# theremin_PCB.net
KiCad netlist of a schematic drawn in EAGLE
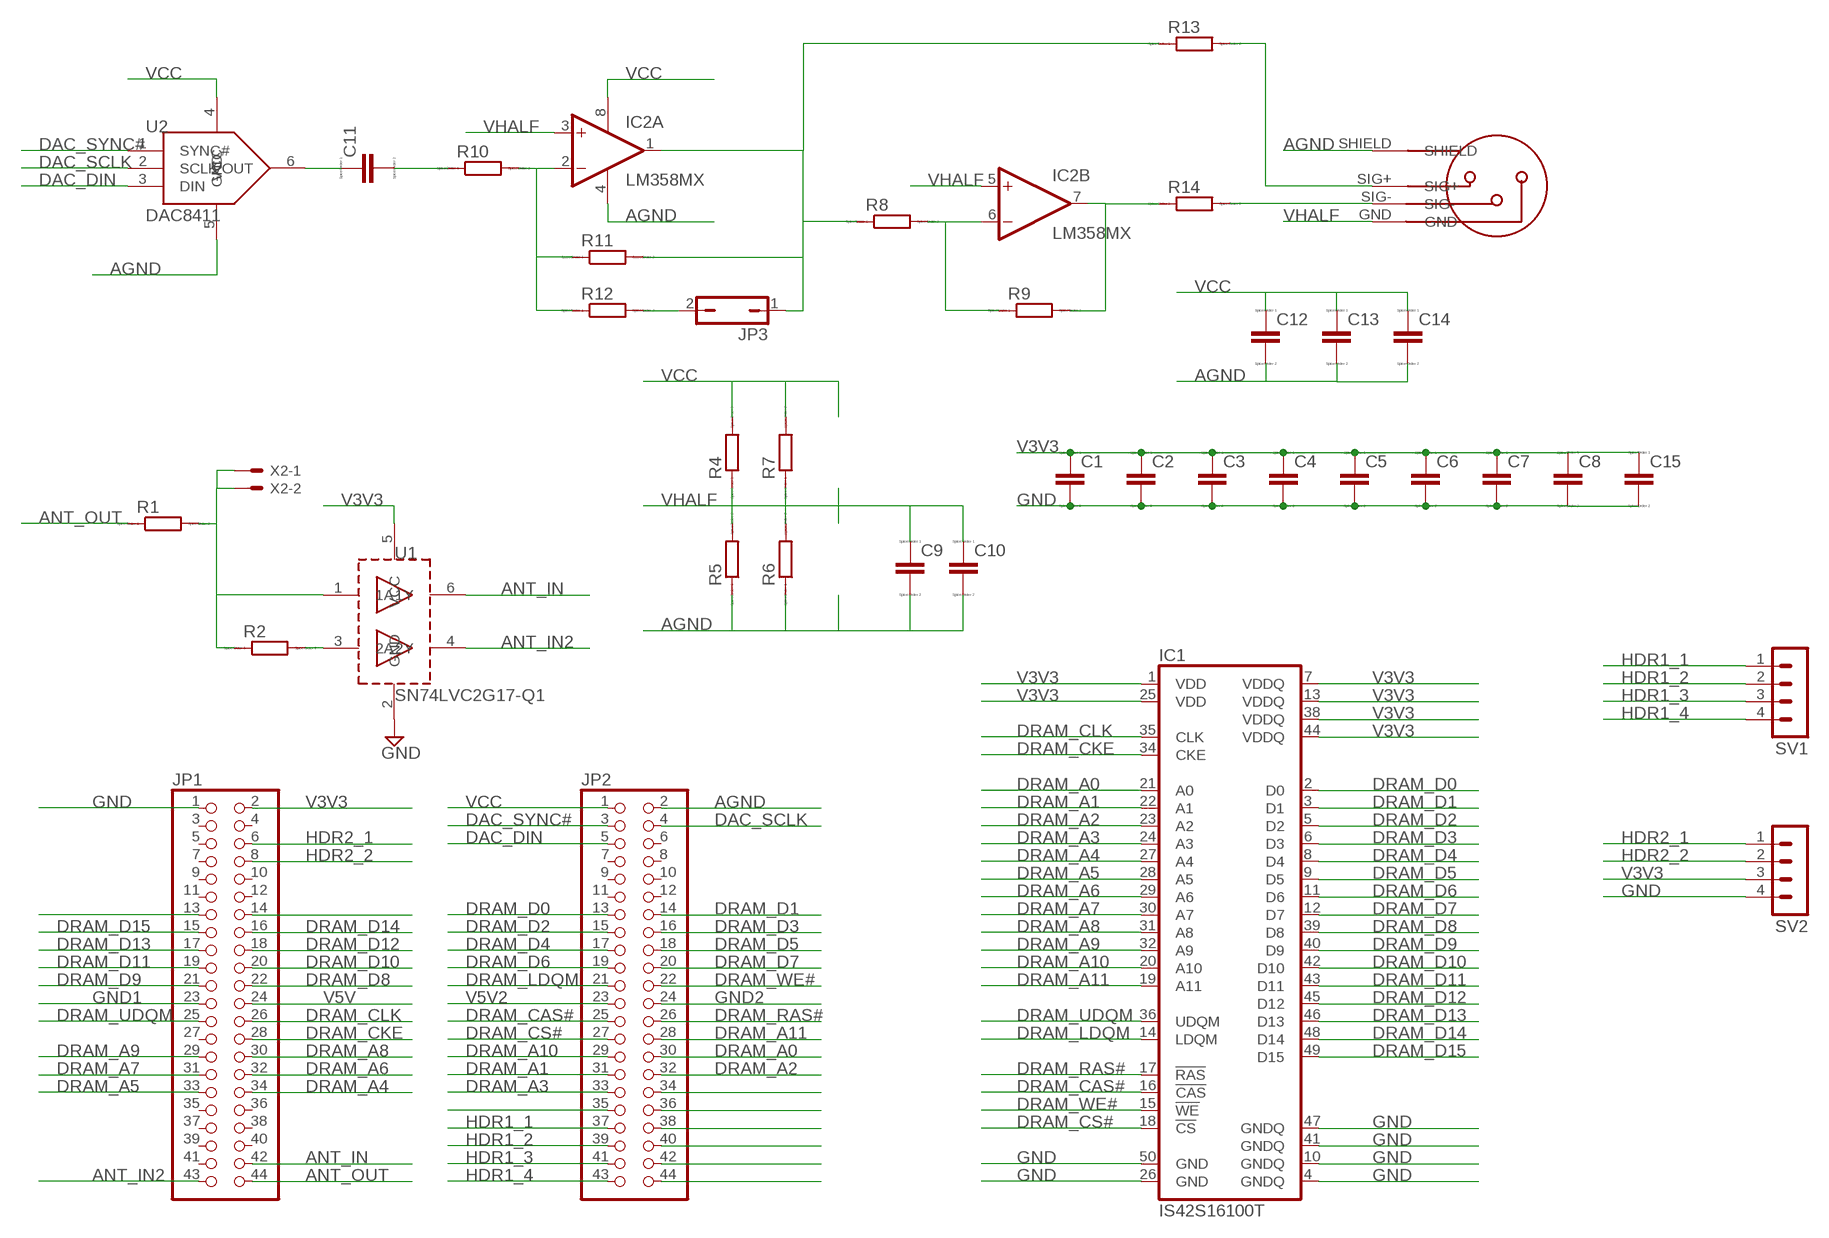
[diagram p0: schematic, sheet 1]

(export (version "E")
  (design (tool "Eeschema 10.0.6"))
  (components
    (comp (ref "C1")
      (value "C-EUC0805")
      (footprint "eagle-import:C0805")
      (libsource (lib "eagle-import") (part "C-EUC0805"))
    )
    (comp (ref "C2")
      (value "C-EUC0805")
      (footprint "eagle-import:C0805")
      (libsource (lib "eagle-import") (part "C-EUC0805"))
    )
    (comp (ref "C3")
      (value "C-EUC0805")
      (footprint "eagle-import:C0805")
      (libsource (lib "eagle-import") (part "C-EUC0805"))
    )
    (comp (ref "C4")
      (value "C-EUC0805")
      (footprint "eagle-import:C0805")
      (libsource (lib "eagle-import") (part "C-EUC0805"))
    )
    (comp (ref "C5")
      (value "C-EUC0805")
      (footprint "eagle-import:C0805")
      (libsource (lib "eagle-import") (part "C-EUC0805"))
    )
    (comp (ref "C6")
      (value "C-EUC0805")
      (footprint "eagle-import:C0805")
      (libsource (lib "eagle-import") (part "C-EUC0805"))
    )
    (comp (ref "C7")
      (value "C-EUC0805")
      (footprint "eagle-import:C0805")
      (libsource (lib "eagle-import") (part "C-EUC0805"))
    )
    (comp (ref "C8")
      (value "C-EUC0805")
      (footprint "eagle-import:C0805")
      (libsource (lib "eagle-import") (part "C-EUC0805"))
    )
    (comp (ref "C9")
      (value "C-EUC0805")
      (footprint "eagle-import:C0805")
      (libsource (lib "eagle-import") (part "C-EUC0805"))
    )
    (comp (ref "C10")
      (value "C-EUC0805")
      (footprint "eagle-import:C0805")
      (libsource (lib "eagle-import") (part "C-EUC0805"))
    )
    (comp (ref "C11")
      (value "C-EUC0805")
      (footprint "eagle-import:C0805")
      (libsource (lib "eagle-import") (part "C-EUC0805"))
    )
    (comp (ref "C12")
      (value "C-EUC0805")
      (footprint "eagle-import:C0805")
      (libsource (lib "eagle-import") (part "C-EUC0805"))
    )
    (comp (ref "C13")
      (value "C-EUC0805")
      (footprint "eagle-import:C0805")
      (libsource (lib "eagle-import") (part "C-EUC0805"))
    )
    (comp (ref "C14")
      (value "C-EUC0805")
      (footprint "eagle-import:C0805")
      (libsource (lib "eagle-import") (part "C-EUC0805"))
    )
    (comp (ref "C15")
      (value "C-EUC0805")
      (footprint "eagle-import:C0805")
      (libsource (lib "eagle-import") (part "C-EUC0805"))
    )
    (comp (ref "IC1")
      (value "IS42S16100T")
      (footprint "eagle-import:TSOP50-II")
      (libsource (lib "eagle-import") (part "IS42S16100T"))
    )
    (comp (ref "IC2")
      (value "LM358MX")
      (footprint "eagle-import:SO08")
      (libsource (lib "eagle-import") (part "LM358MX"))
    )
    (comp (ref "JP1")
      (value "PINHD-2X22")
      (footprint "eagle-import:2X22")
      (libsource (lib "eagle-import") (part "PINHD-2X22"))
    )
    (comp (ref "JP2")
      (value "PINHD-2X22")
      (footprint "eagle-import:2X22")
      (libsource (lib "eagle-import") (part "PINHD-2X22"))
    )
    (comp (ref "JP3")
      (value "JP1Q")
      (footprint "eagle-import:JP1")
      (libsource (lib "eagle-import") (part "JP1Q"))
    )
    (comp (ref "R1")
      (value "R-EU_R0603")
      (footprint "eagle-import:R0603")
      (libsource (lib "eagle-import") (part "R-EU_R0603"))
    )
    (comp (ref "R2")
      (value "R-EU_R0603")
      (footprint "eagle-import:R0603")
      (libsource (lib "eagle-import") (part "R-EU_R0603"))
    )
    (comp (ref "R4")
      (value "R-EU_M0805")
      (footprint "eagle-import:M0805")
      (libsource (lib "eagle-import") (part "R-EU_M0805"))
    )
    (comp (ref "R5")
      (value "R-EU_M0805")
      (footprint "eagle-import:M0805")
      (libsource (lib "eagle-import") (part "R-EU_M0805"))
    )
    (comp (ref "R6")
      (value "R-EU_M0805")
      (footprint "eagle-import:M0805")
      (libsource (lib "eagle-import") (part "R-EU_M0805"))
    )
    (comp (ref "R7")
      (value "R-EU_M0805")
      (footprint "eagle-import:M0805")
      (libsource (lib "eagle-import") (part "R-EU_M0805"))
    )
    (comp (ref "R8")
      (value "R-EU_M0805")
      (footprint "eagle-import:M0805")
      (libsource (lib "eagle-import") (part "R-EU_M0805"))
    )
    (comp (ref "R9")
      (value "R-EU_M0805")
      (footprint "eagle-import:M0805")
      (libsource (lib "eagle-import") (part "R-EU_M0805"))
    )
    (comp (ref "R10")
      (value "R-EU_M0805")
      (footprint "eagle-import:M0805")
      (libsource (lib "eagle-import") (part "R-EU_M0805"))
    )
    (comp (ref "R11")
      (value "R-EU_M0805")
      (footprint "eagle-import:M0805")
      (libsource (lib "eagle-import") (part "R-EU_M0805"))
    )
    (comp (ref "R12")
      (value "R-EU_M0805")
      (footprint "eagle-import:M0805")
      (libsource (lib "eagle-import") (part "R-EU_M0805"))
    )
    (comp (ref "R13")
      (value "R-EU_M0805")
      (footprint "eagle-import:M0805")
      (libsource (lib "eagle-import") (part "R-EU_M0805"))
    )
    (comp (ref "R14")
      (value "R-EU_M0805")
      (footprint "eagle-import:M0805")
      (libsource (lib "eagle-import") (part "R-EU_M0805"))
    )
    (comp (ref "SV1")
      (value "MA04-1")
      (footprint "eagle-import:MA04-1")
      (libsource (lib "eagle-import") (part "MA04-1"))
    )
    (comp (ref "SV2")
      (value "MA04-1")
      (footprint "eagle-import:MA04-1")
      (libsource (lib "eagle-import") (part "MA04-1"))
    )
    (comp (ref "U$1")
      (value "MINIXLR")
      (footprint "eagle-import:MINXLR")
      (libsource (lib "eagle-import") (part "MINIXLR"))
    )
    (comp (ref "U1")
      (value "SN74LVC2G17-Q1")
      (footprint "eagle-import:DCK_R-PDSO-G6")
      (libsource (lib "eagle-import") (part "SN74LVC2G17-Q1"))
    )
    (comp (ref "U2")
      (value "DAC8411")
      (footprint "eagle-import:DCK_R-PDSO-G6")
      (libsource (lib "eagle-import") (part "DAC8411"))
    )
    (comp (ref "X2")
      (value "KK-156-2")
      (footprint "eagle-import:KK-156-2")
      (libsource (lib "eagle-import") (part "KK-156-2"))
    )
  )
  (nets
    (net (code "1") (name "/AGND") (class "Default")
      (node (ref "C10") (pin "2") (pinfunction "2_2") (pintype "passive"))
      (node (ref "C12") (pin "2") (pinfunction "2_2") (pintype "passive"))
      (node (ref "C13") (pin "2") (pinfunction "2_2") (pintype "passive"))
      (node (ref "C14") (pin "2") (pinfunction "2_2") (pintype "passive"))
      (node (ref "C9") (pin "2") (pinfunction "2_2") (pintype "passive"))
      (node (ref "IC2") (pin "4") (pinfunction "V-_4") (pintype "power_in"))
      (node (ref "JP2") (pin "2") (pinfunction "2_2") (pintype "passive"))
      (node (ref "R5") (pin "1") (pinfunction "1_1") (pintype "passive"))
      (node (ref "R6") (pin "1") (pinfunction "1_1") (pintype "passive"))
      (node (ref "U$1") (pin "SHIELD") (pinfunction "SHIELD_SHIELD") (pintype "bidirectional"))
      (node (ref "U2") (pin "5") (pinfunction "GND_5") (pintype "bidirectional"))
    )
    (net (code "2") (name "/ANT_IN") (class "Default")
      (node (ref "JP1") (pin "42") (pinfunction "42_42") (pintype "passive"))
      (node (ref "U1") (pin "6") (pinfunction "1Y_6") (pintype "bidirectional"))
    )
    (net (code "3") (name "/ANT_IN2") (class "Default")
      (node (ref "JP1") (pin "43") (pinfunction "43_43") (pintype "passive"))
      (node (ref "U1") (pin "4") (pinfunction "2Y_4") (pintype "bidirectional"))
    )
    (net (code "4") (name "/ANT_OUT") (class "Default")
      (node (ref "JP1") (pin "44") (pinfunction "44_44") (pintype "passive"))
      (node (ref "R1") (pin "1") (pinfunction "1_1") (pintype "passive"))
    )
    (net (code "5") (name "/DAC_DIN") (class "Default")
      (node (ref "JP2") (pin "5") (pinfunction "5_5") (pintype "passive"))
      (node (ref "U2") (pin "3") (pinfunction "DIN_3") (pintype "bidirectional"))
    )
    (net (code "6") (name "/DAC_SCLK") (class "Default")
      (node (ref "JP2") (pin "4") (pinfunction "4_4") (pintype "passive"))
      (node (ref "U2") (pin "2") (pinfunction "SCLK_2") (pintype "bidirectional"))
    )
    (net (code "7") (name "/DAC_SYNC#") (class "Default")
      (node (ref "JP2") (pin "3") (pinfunction "3_3") (pintype "passive"))
      (node (ref "U2") (pin "1") (pinfunction "SYNC#_1") (pintype "bidirectional"))
    )
    (net (code "8") (name "/DRAM_A0") (class "Default")
      (node (ref "IC1") (pin "21") (pinfunction "A0_21") (pintype "input"))
      (node (ref "JP2") (pin "30") (pinfunction "30_30") (pintype "passive"))
    )
    (net (code "9") (name "/DRAM_A1") (class "Default")
      (node (ref "IC1") (pin "22") (pinfunction "A1_22") (pintype "input"))
      (node (ref "JP2") (pin "31") (pinfunction "31_31") (pintype "passive"))
    )
    (net (code "10") (name "/DRAM_A2") (class "Default")
      (node (ref "IC1") (pin "23") (pinfunction "A2_23") (pintype "input"))
      (node (ref "JP2") (pin "32") (pinfunction "32_32") (pintype "passive"))
    )
    (net (code "11") (name "/DRAM_A3") (class "Default")
      (node (ref "IC1") (pin "24") (pinfunction "A3_24") (pintype "input"))
      (node (ref "JP2") (pin "33") (pinfunction "33_33") (pintype "passive"))
    )
    (net (code "12") (name "/DRAM_A4") (class "Default")
      (node (ref "IC1") (pin "27") (pinfunction "A4_27") (pintype "input"))
      (node (ref "JP1") (pin "34") (pinfunction "34_34") (pintype "passive"))
    )
    (net (code "13") (name "/DRAM_A5") (class "Default")
      (node (ref "IC1") (pin "28") (pinfunction "A5_28") (pintype "input"))
      (node (ref "JP1") (pin "33") (pinfunction "33_33") (pintype "passive"))
    )
    (net (code "14") (name "/DRAM_A6") (class "Default")
      (node (ref "IC1") (pin "29") (pinfunction "A6_29") (pintype "input"))
      (node (ref "JP1") (pin "32") (pinfunction "32_32") (pintype "passive"))
    )
    (net (code "15") (name "/DRAM_A7") (class "Default")
      (node (ref "IC1") (pin "30") (pinfunction "A7_30") (pintype "input"))
      (node (ref "JP1") (pin "31") (pinfunction "31_31") (pintype "passive"))
    )
    (net (code "16") (name "/DRAM_A8") (class "Default")
      (node (ref "IC1") (pin "31") (pinfunction "A8_31") (pintype "input"))
      (node (ref "JP1") (pin "30") (pinfunction "30_30") (pintype "passive"))
    )
    (net (code "17") (name "/DRAM_A9") (class "Default")
      (node (ref "IC1") (pin "32") (pinfunction "A9_32") (pintype "input"))
      (node (ref "JP1") (pin "29") (pinfunction "29_29") (pintype "passive"))
    )
    (net (code "18") (name "/DRAM_A10") (class "Default")
      (node (ref "IC1") (pin "20") (pinfunction "A10_20") (pintype "input"))
      (node (ref "JP2") (pin "29") (pinfunction "29_29") (pintype "passive"))
    )
    (net (code "19") (name "/DRAM_A11") (class "Default")
      (node (ref "IC1") (pin "19") (pinfunction "A11_19") (pintype "input"))
      (node (ref "JP2") (pin "28") (pinfunction "28_28") (pintype "passive"))
    )
    (net (code "20") (name "/DRAM_CAS#") (class "Default")
      (node (ref "IC1") (pin "16") (pinfunction "~{CAS}_16") (pintype "input"))
      (node (ref "JP2") (pin "25") (pinfunction "25_25") (pintype "passive"))
    )
    (net (code "21") (name "/DRAM_CKE") (class "Default")
      (node (ref "IC1") (pin "34") (pinfunction "CKE_34") (pintype "input"))
      (node (ref "JP1") (pin "28") (pinfunction "28_28") (pintype "passive"))
    )
    (net (code "22") (name "/DRAM_CLK") (class "Default")
      (node (ref "IC1") (pin "35") (pinfunction "CLK_35") (pintype "input"))
      (node (ref "JP1") (pin "26") (pinfunction "26_26") (pintype "passive"))
    )
    (net (code "23") (name "/DRAM_CS#") (class "Default")
      (node (ref "IC1") (pin "18") (pinfunction "~{CS}_18") (pintype "input"))
      (node (ref "JP2") (pin "27") (pinfunction "27_27") (pintype "passive"))
    )
    (net (code "24") (name "/DRAM_D0") (class "Default")
      (node (ref "IC1") (pin "2") (pinfunction "D0_2") (pintype "bidirectional"))
      (node (ref "JP2") (pin "13") (pinfunction "13_13") (pintype "passive"))
    )
    (net (code "25") (name "/DRAM_D1") (class "Default")
      (node (ref "IC1") (pin "3") (pinfunction "D1_3") (pintype "bidirectional"))
      (node (ref "JP2") (pin "14") (pinfunction "14_14") (pintype "passive"))
    )
    (net (code "26") (name "/DRAM_D2") (class "Default")
      (node (ref "IC1") (pin "5") (pinfunction "D2_5") (pintype "bidirectional"))
      (node (ref "JP2") (pin "15") (pinfunction "15_15") (pintype "passive"))
    )
    (net (code "27") (name "/DRAM_D3") (class "Default")
      (node (ref "IC1") (pin "6") (pinfunction "D3_6") (pintype "bidirectional"))
      (node (ref "JP2") (pin "16") (pinfunction "16_16") (pintype "passive"))
    )
    (net (code "28") (name "/DRAM_D4") (class "Default")
      (node (ref "IC1") (pin "8") (pinfunction "D4_8") (pintype "bidirectional"))
      (node (ref "JP2") (pin "17") (pinfunction "17_17") (pintype "passive"))
    )
    (net (code "29") (name "/DRAM_D5") (class "Default")
      (node (ref "IC1") (pin "9") (pinfunction "D5_9") (pintype "bidirectional"))
      (node (ref "JP2") (pin "18") (pinfunction "18_18") (pintype "passive"))
    )
    (net (code "30") (name "/DRAM_D6") (class "Default")
      (node (ref "IC1") (pin "11") (pinfunction "D6_11") (pintype "bidirectional"))
      (node (ref "JP2") (pin "19") (pinfunction "19_19") (pintype "passive"))
    )
    (net (code "31") (name "/DRAM_D7") (class "Default")
      (node (ref "IC1") (pin "12") (pinfunction "D7_12") (pintype "bidirectional"))
      (node (ref "JP2") (pin "20") (pinfunction "20_20") (pintype "passive"))
    )
    (net (code "32") (name "/DRAM_D8") (class "Default")
      (node (ref "IC1") (pin "39") (pinfunction "D8_39") (pintype "bidirectional"))
      (node (ref "JP1") (pin "22") (pinfunction "22_22") (pintype "passive"))
    )
    (net (code "33") (name "/DRAM_D9") (class "Default")
      (node (ref "IC1") (pin "40") (pinfunction "D9_40") (pintype "bidirectional"))
      (node (ref "JP1") (pin "21") (pinfunction "21_21") (pintype "passive"))
    )
    (net (code "34") (name "/DRAM_D10") (class "Default")
      (node (ref "IC1") (pin "42") (pinfunction "D10_42") (pintype "bidirectional"))
      (node (ref "JP1") (pin "20") (pinfunction "20_20") (pintype "passive"))
    )
    (net (code "35") (name "/DRAM_D11") (class "Default")
      (node (ref "IC1") (pin "43") (pinfunction "D11_43") (pintype "bidirectional"))
      (node (ref "JP1") (pin "19") (pinfunction "19_19") (pintype "passive"))
    )
    (net (code "36") (name "/DRAM_D12") (class "Default")
      (node (ref "IC1") (pin "45") (pinfunction "D12_45") (pintype "bidirectional"))
      (node (ref "JP1") (pin "18") (pinfunction "18_18") (pintype "passive"))
    )
    (net (code "37") (name "/DRAM_D13") (class "Default")
      (node (ref "IC1") (pin "46") (pinfunction "D13_46") (pintype "bidirectional"))
      (node (ref "JP1") (pin "17") (pinfunction "17_17") (pintype "passive"))
    )
    (net (code "38") (name "/DRAM_D14") (class "Default")
      (node (ref "IC1") (pin "48") (pinfunction "D14_48") (pintype "bidirectional"))
      (node (ref "JP1") (pin "16") (pinfunction "16_16") (pintype "passive"))
    )
    (net (code "39") (name "/DRAM_D15") (class "Default")
      (node (ref "IC1") (pin "49") (pinfunction "D15_49") (pintype "bidirectional"))
      (node (ref "JP1") (pin "15") (pinfunction "15_15") (pintype "passive"))
    )
    (net (code "40") (name "/DRAM_LDQM") (class "Default")
      (node (ref "IC1") (pin "14") (pinfunction "LDQM_14") (pintype "input"))
      (node (ref "JP2") (pin "21") (pinfunction "21_21") (pintype "passive"))
    )
    (net (code "41") (name "/DRAM_RAS#") (class "Default")
      (node (ref "IC1") (pin "17") (pinfunction "~{RAS}_17") (pintype "input"))
      (node (ref "JP2") (pin "26") (pinfunction "26_26") (pintype "passive"))
    )
    (net (code "42") (name "/DRAM_UDQM") (class "Default")
      (node (ref "IC1") (pin "36") (pinfunction "UDQM_36") (pintype "input"))
      (node (ref "JP1") (pin "25") (pinfunction "25_25") (pintype "passive"))
    )
    (net (code "43") (name "/DRAM_WE#") (class "Default")
      (node (ref "IC1") (pin "15") (pinfunction "~{WE}_15") (pintype "input"))
      (node (ref "JP2") (pin "22") (pinfunction "22_22") (pintype "passive"))
    )
    (net (code "44") (name "/GND1") (class "Default")
      (node (ref "JP1") (pin "23") (pinfunction "23_23") (pintype "passive"))
    )
    (net (code "45") (name "/GND2") (class "Default")
      (node (ref "JP2") (pin "24") (pinfunction "24_24") (pintype "passive"))
    )
    (net (code "46") (name "/HDR1_1") (class "Default")
      (node (ref "JP2") (pin "37") (pinfunction "37_37") (pintype "passive"))
      (node (ref "SV1") (pin "1") (pinfunction "1_1") (pintype "passive"))
    )
    (net (code "47") (name "/HDR1_2") (class "Default")
      (node (ref "JP2") (pin "39") (pinfunction "39_39") (pintype "passive"))
      (node (ref "SV1") (pin "2") (pinfunction "2_2") (pintype "passive"))
    )
    (net (code "48") (name "/HDR1_3") (class "Default")
      (node (ref "JP2") (pin "41") (pinfunction "41_41") (pintype "passive"))
      (node (ref "SV1") (pin "3") (pinfunction "3_3") (pintype "passive"))
    )
    (net (code "49") (name "/HDR1_4") (class "Default")
      (node (ref "JP2") (pin "43") (pinfunction "43_43") (pintype "passive"))
      (node (ref "SV1") (pin "4") (pinfunction "4_4") (pintype "passive"))
    )
    (net (code "50") (name "/HDR2_1") (class "Default")
      (node (ref "JP1") (pin "6") (pinfunction "6_6") (pintype "passive"))
      (node (ref "SV2") (pin "1") (pinfunction "1_1") (pintype "passive"))
    )
    (net (code "51") (name "/HDR2_2") (class "Default")
      (node (ref "JP1") (pin "8") (pinfunction "8_8") (pintype "passive"))
      (node (ref "SV2") (pin "2") (pinfunction "2_2") (pintype "passive"))
    )
    (net (code "52") (name "/V3V3") (class "Default")
      (node (ref "C1") (pin "1") (pinfunction "1_1") (pintype "passive"))
      (node (ref "C15") (pin "1") (pinfunction "1_1") (pintype "passive"))
      (node (ref "C2") (pin "1") (pinfunction "1_1") (pintype "passive"))
      (node (ref "C3") (pin "1") (pinfunction "1_1") (pintype "passive"))
      (node (ref "C4") (pin "1") (pinfunction "1_1") (pintype "passive"))
      (node (ref "C5") (pin "1") (pinfunction "1_1") (pintype "passive"))
      (node (ref "C6") (pin "1") (pinfunction "1_1") (pintype "passive"))
      (node (ref "C7") (pin "1") (pinfunction "1_1") (pintype "passive"))
      (node (ref "C8") (pin "1") (pinfunction "1_1") (pintype "passive"))
      (node (ref "IC1") (pin "1") (pinfunction "VDD_1") (pintype "power_in"))
      (node (ref "IC1") (pin "13") (pinfunction "VDDQ_13") (pintype "power_in"))
      (node (ref "IC1") (pin "25") (pinfunction "VDD_25") (pintype "power_in"))
      (node (ref "IC1") (pin "38") (pinfunction "VDDQ_38") (pintype "power_in"))
      (node (ref "IC1") (pin "44") (pinfunction "VDDQ_44") (pintype "power_in"))
      (node (ref "IC1") (pin "7") (pinfunction "VDDQ_7") (pintype "power_in"))
      (node (ref "JP1") (pin "2") (pinfunction "2_2") (pintype "passive"))
      (node (ref "SV2") (pin "3") (pinfunction "3_3") (pintype "passive"))
      (node (ref "U1") (pin "5") (pinfunction "VCC_5") (pintype "bidirectional"))
    )
    (net (code "53") (name "/V5V") (class "Default")
      (node (ref "JP1") (pin "24") (pinfunction "24_24") (pintype "passive"))
    )
    (net (code "54") (name "/V5V2") (class "Default")
      (node (ref "JP2") (pin "23") (pinfunction "23_23") (pintype "passive"))
    )
    (net (code "55") (name "/VCC") (class "Default")
      (node (ref "C12") (pin "1") (pinfunction "1_1") (pintype "passive"))
      (node (ref "C13") (pin "1") (pinfunction "1_1") (pintype "passive"))
      (node (ref "C14") (pin "1") (pinfunction "1_1") (pintype "passive"))
      (node (ref "IC2") (pin "8") (pinfunction "V+_8") (pintype "power_in"))
      (node (ref "JP2") (pin "1") (pinfunction "1_1") (pintype "passive"))
      (node (ref "R4") (pin "2") (pinfunction "2_2") (pintype "passive"))
      (node (ref "R7") (pin "2") (pinfunction "2_2") (pintype "passive"))
      (node (ref "U2") (pin "4") (pinfunction "VCC_4") (pintype "bidirectional"))
    )
    (net (code "56") (name "/VHALF") (class "Default")
      (node (ref "C10") (pin "1") (pinfunction "1_1") (pintype "passive"))
      (node (ref "C9") (pin "1") (pinfunction "1_1") (pintype "passive"))
      (node (ref "IC2") (pin "3") (pinfunction "+IN_3") (pintype "input"))
      (node (ref "IC2") (pin "5") (pinfunction "+IN_5") (pintype "input"))
      (node (ref "R4") (pin "1") (pinfunction "1_1") (pintype "passive"))
      (node (ref "R5") (pin "2") (pinfunction "2_2") (pintype "passive"))
      (node (ref "R6") (pin "2") (pinfunction "2_2") (pintype "passive"))
      (node (ref "R7") (pin "1") (pinfunction "1_1") (pintype "passive"))
      (node (ref "U$1") (pin "GND") (pinfunction "GND_GND") (pintype "bidirectional"))
    )
    (net (code "57") (name "GND") (class "Default")
      (node (ref "C1") (pin "2") (pinfunction "2_2") (pintype "passive"))
      (node (ref "C15") (pin "2") (pinfunction "2_2") (pintype "passive"))
      (node (ref "C2") (pin "2") (pinfunction "2_2") (pintype "passive"))
      (node (ref "C3") (pin "2") (pinfunction "2_2") (pintype "passive"))
      (node (ref "C4") (pin "2") (pinfunction "2_2") (pintype "passive"))
      (node (ref "C5") (pin "2") (pinfunction "2_2") (pintype "passive"))
      (node (ref "C6") (pin "2") (pinfunction "2_2") (pintype "passive"))
      (node (ref "C7") (pin "2") (pinfunction "2_2") (pintype "passive"))
      (node (ref "C8") (pin "2") (pinfunction "2_2") (pintype "passive"))
      (node (ref "IC1") (pin "10") (pinfunction "GNDQ_10") (pintype "power_in"))
      (node (ref "IC1") (pin "26") (pinfunction "GND_26") (pintype "power_in"))
      (node (ref "IC1") (pin "4") (pinfunction "GNDQ_4") (pintype "power_in"))
      (node (ref "IC1") (pin "41") (pinfunction "GNDQ_41") (pintype "power_in"))
      (node (ref "IC1") (pin "47") (pinfunction "GNDQ_47") (pintype "power_in"))
      (node (ref "IC1") (pin "50") (pinfunction "GND_50") (pintype "power_in"))
      (node (ref "JP1") (pin "1") (pinfunction "1_1") (pintype "passive"))
      (node (ref "SV2") (pin "4") (pinfunction "4_4") (pintype "passive"))
      (node (ref "U1") (pin "2") (pinfunction "GND_2") (pintype "bidirectional"))
    )
    (net (code "58") (name "Net-(C11-Pad2)") (class "Default")
      (node (ref "C11") (pin "2") (pinfunction "2_2") (pintype "passive"))
      (node (ref "R10") (pin "1") (pinfunction "1_1") (pintype "passive"))
    )
    (net (code "59") (name "Net-(IC2A--IN)") (class "Default")
      (node (ref "IC2") (pin "2") (pinfunction "-IN_2") (pintype "input"))
      (node (ref "R10") (pin "2") (pinfunction "2_2") (pintype "passive"))
      (node (ref "R11") (pin "1") (pinfunction "1_1") (pintype "passive"))
      (node (ref "R12") (pin "1") (pinfunction "1_1") (pintype "passive"))
    )
    (net (code "60") (name "Net-(IC2A-OUT)") (class "Default")
      (node (ref "IC2") (pin "1") (pinfunction "OUT_1") (pintype "output"))
      (node (ref "JP3") (pin "1") (pinfunction "1_1") (pintype "passive"))
      (node (ref "R11") (pin "2") (pinfunction "2_2") (pintype "passive"))
      (node (ref "R13") (pin "1") (pinfunction "1_1") (pintype "passive"))
      (node (ref "R8") (pin "1") (pinfunction "1_1") (pintype "passive"))
    )
    (net (code "61") (name "Net-(IC2B--IN)") (class "Default")
      (node (ref "IC2") (pin "6") (pinfunction "-IN_6") (pintype "input"))
      (node (ref "R8") (pin "2") (pinfunction "2_2") (pintype "passive"))
      (node (ref "R9") (pin "1") (pinfunction "1_1") (pintype "passive"))
    )
    (net (code "62") (name "Net-(IC2B-OUT)") (class "Default")
      (node (ref "IC2") (pin "7") (pinfunction "OUT_7") (pintype "output"))
      (node (ref "R14") (pin "1") (pinfunction "1_1") (pintype "passive"))
      (node (ref "R9") (pin "2") (pinfunction "2_2") (pintype "passive"))
    )
    (net (code "63") (name "Net-(JP3-Pad2)") (class "Default")
      (node (ref "JP3") (pin "2") (pinfunction "2_2") (pintype "passive"))
      (node (ref "R12") (pin "2") (pinfunction "2_2") (pintype "passive"))
    )
    (net (code "64") (name "Net-(R13-Pad2)") (class "Default")
      (node (ref "R13") (pin "2") (pinfunction "2_2") (pintype "passive"))
      (node (ref "U$1") (pin "SIG+") (pinfunction "SIG+_SIG+") (pintype "bidirectional"))
    )
    (net (code "65") (name "Net-(R14-Pad2)") (class "Default")
      (node (ref "R14") (pin "2") (pinfunction "2_2") (pintype "passive"))
      (node (ref "U$1") (pin "SIG-") (pinfunction "SIG-_SIG-") (pintype "bidirectional"))
    )
    (net (code "66") (name "Net-(U1-1A)") (class "Default")
      (node (ref "R1") (pin "2") (pinfunction "2_2") (pintype "passive"))
      (node (ref "R2") (pin "1") (pinfunction "1_1") (pintype "passive"))
      (node (ref "U1") (pin "1") (pinfunction "1A_1") (pintype "bidirectional"))
      (node (ref "X2") (pin "1") (pinfunction "S_1") (pintype "passive"))
      (node (ref "X2") (pin "2") (pinfunction "S_2") (pintype "passive"))
    )
    (net (code "67") (name "Net-(U1-2A)") (class "Default")
      (node (ref "R2") (pin "2") (pinfunction "2_2") (pintype "passive"))
      (node (ref "U1") (pin "3") (pinfunction "2A_3") (pintype "bidirectional"))
    )
    (net (code "68") (name "Net-(U2-VOUT)") (class "Default")
      (node (ref "C11") (pin "1") (pinfunction "1_1") (pintype "passive"))
      (node (ref "U2") (pin "6") (pinfunction "VOUT_6") (pintype "bidirectional"))
    )
    (net (code "69") (name "unconnected-(JP1-Pad3)") (class "Default")
      (node (ref "JP1") (pin "3") (pinfunction "3_3") (pintype "passive"))
    )
    (net (code "70") (name "unconnected-(JP1-Pad4)") (class "Default")
      (node (ref "JP1") (pin "4") (pinfunction "4_4") (pintype "passive"))
    )
    (net (code "71") (name "unconnected-(JP1-Pad5)") (class "Default")
      (node (ref "JP1") (pin "5") (pinfunction "5_5") (pintype "passive"))
    )
    (net (code "72") (name "unconnected-(JP1-Pad7)") (class "Default")
      (node (ref "JP1") (pin "7") (pinfunction "7_7") (pintype "passive"))
    )
    (net (code "73") (name "unconnected-(JP1-Pad9)") (class "Default")
      (node (ref "JP1") (pin "9") (pinfunction "9_9") (pintype "passive"))
    )
    (net (code "74") (name "unconnected-(JP1-Pad10)") (class "Default")
      (node (ref "JP1") (pin "10") (pinfunction "10_10") (pintype "passive"))
    )
    (net (code "75") (name "unconnected-(JP1-Pad11)") (class "Default")
      (node (ref "JP1") (pin "11") (pinfunction "11_11") (pintype "passive"))
    )
    (net (code "76") (name "unconnected-(JP1-Pad12)") (class "Default")
      (node (ref "JP1") (pin "12") (pinfunction "12_12") (pintype "passive"))
    )
    (net (code "77") (name "unconnected-(JP1-Pad13)") (class "Default")
      (node (ref "JP1") (pin "13") (pinfunction "13_13") (pintype "passive"))
    )
    (net (code "78") (name "unconnected-(JP1-Pad14)") (class "Default")
      (node (ref "JP1") (pin "14") (pinfunction "14_14") (pintype "passive"))
    )
    (net (code "79") (name "unconnected-(JP1-Pad27)") (class "Default")
      (node (ref "JP1") (pin "27") (pinfunction "27_27") (pintype "passive"))
    )
    (net (code "80") (name "unconnected-(JP1-Pad35)") (class "Default")
      (node (ref "JP1") (pin "35") (pinfunction "35_35") (pintype "passive"))
    )
    (net (code "81") (name "unconnected-(JP1-Pad36)") (class "Default")
      (node (ref "JP1") (pin "36") (pinfunction "36_36") (pintype "passive"))
    )
    (net (code "82") (name "unconnected-(JP1-Pad37)") (class "Default")
      (node (ref "JP1") (pin "37") (pinfunction "37_37") (pintype "passive"))
    )
    (net (code "83") (name "unconnected-(JP1-Pad38)") (class "Default")
      (node (ref "JP1") (pin "38") (pinfunction "38_38") (pintype "passive"))
    )
    (net (code "84") (name "unconnected-(JP1-Pad39)") (class "Default")
      (node (ref "JP1") (pin "39") (pinfunction "39_39") (pintype "passive"))
    )
    (net (code "85") (name "unconnected-(JP1-Pad40)") (class "Default")
      (node (ref "JP1") (pin "40") (pinfunction "40_40") (pintype "passive"))
    )
    (net (code "86") (name "unconnected-(JP1-Pad41)") (class "Default")
      (node (ref "JP1") (pin "41") (pinfunction "41_41") (pintype "passive"))
    )
    (net (code "87") (name "unconnected-(JP2-Pad6)") (class "Default")
      (node (ref "JP2") (pin "6") (pinfunction "6_6") (pintype "passive"))
    )
    (net (code "88") (name "unconnected-(JP2-Pad7)") (class "Default")
      (node (ref "JP2") (pin "7") (pinfunction "7_7") (pintype "passive"))
    )
    (net (code "89") (name "unconnected-(JP2-Pad8)") (class "Default")
      (node (ref "JP2") (pin "8") (pinfunction "8_8") (pintype "passive"))
    )
    (net (code "90") (name "unconnected-(JP2-Pad9)") (class "Default")
      (node (ref "JP2") (pin "9") (pinfunction "9_9") (pintype "passive"))
    )
    (net (code "91") (name "unconnected-(JP2-Pad10)") (class "Default")
      (node (ref "JP2") (pin "10") (pinfunction "10_10") (pintype "passive"))
    )
    (net (code "92") (name "unconnected-(JP2-Pad11)") (class "Default")
      (node (ref "JP2") (pin "11") (pinfunction "11_11") (pintype "passive"))
    )
    (net (code "93") (name "unconnected-(JP2-Pad12)") (class "Default")
      (node (ref "JP2") (pin "12") (pinfunction "12_12") (pintype "passive"))
    )
    (net (code "94") (name "unconnected-(JP2-Pad34)") (class "Default")
      (node (ref "JP2") (pin "34") (pinfunction "34_34") (pintype "passive"))
    )
    (net (code "95") (name "unconnected-(JP2-Pad35)") (class "Default")
      (node (ref "JP2") (pin "35") (pinfunction "35_35") (pintype "passive"))
    )
    (net (code "96") (name "unconnected-(JP2-Pad36)") (class "Default")
      (node (ref "JP2") (pin "36") (pinfunction "36_36") (pintype "passive"))
    )
    (net (code "97") (name "unconnected-(JP2-Pad38)") (class "Default")
      (node (ref "JP2") (pin "38") (pinfunction "38_38") (pintype "passive"))
    )
    (net (code "98") (name "unconnected-(JP2-Pad40)") (class "Default")
      (node (ref "JP2") (pin "40") (pinfunction "40_40") (pintype "passive"))
    )
    (net (code "99") (name "unconnected-(JP2-Pad42)") (class "Default")
      (node (ref "JP2") (pin "42") (pinfunction "42_42") (pintype "passive"))
    )
    (net (code "100") (name "unconnected-(JP2-Pad44)") (class "Default")
      (node (ref "JP2") (pin "44") (pinfunction "44_44") (pintype "passive"))
    )
  )
)
